# Dice_Simulator.net
KiCad netlist of a schematic drawn in EAGLE
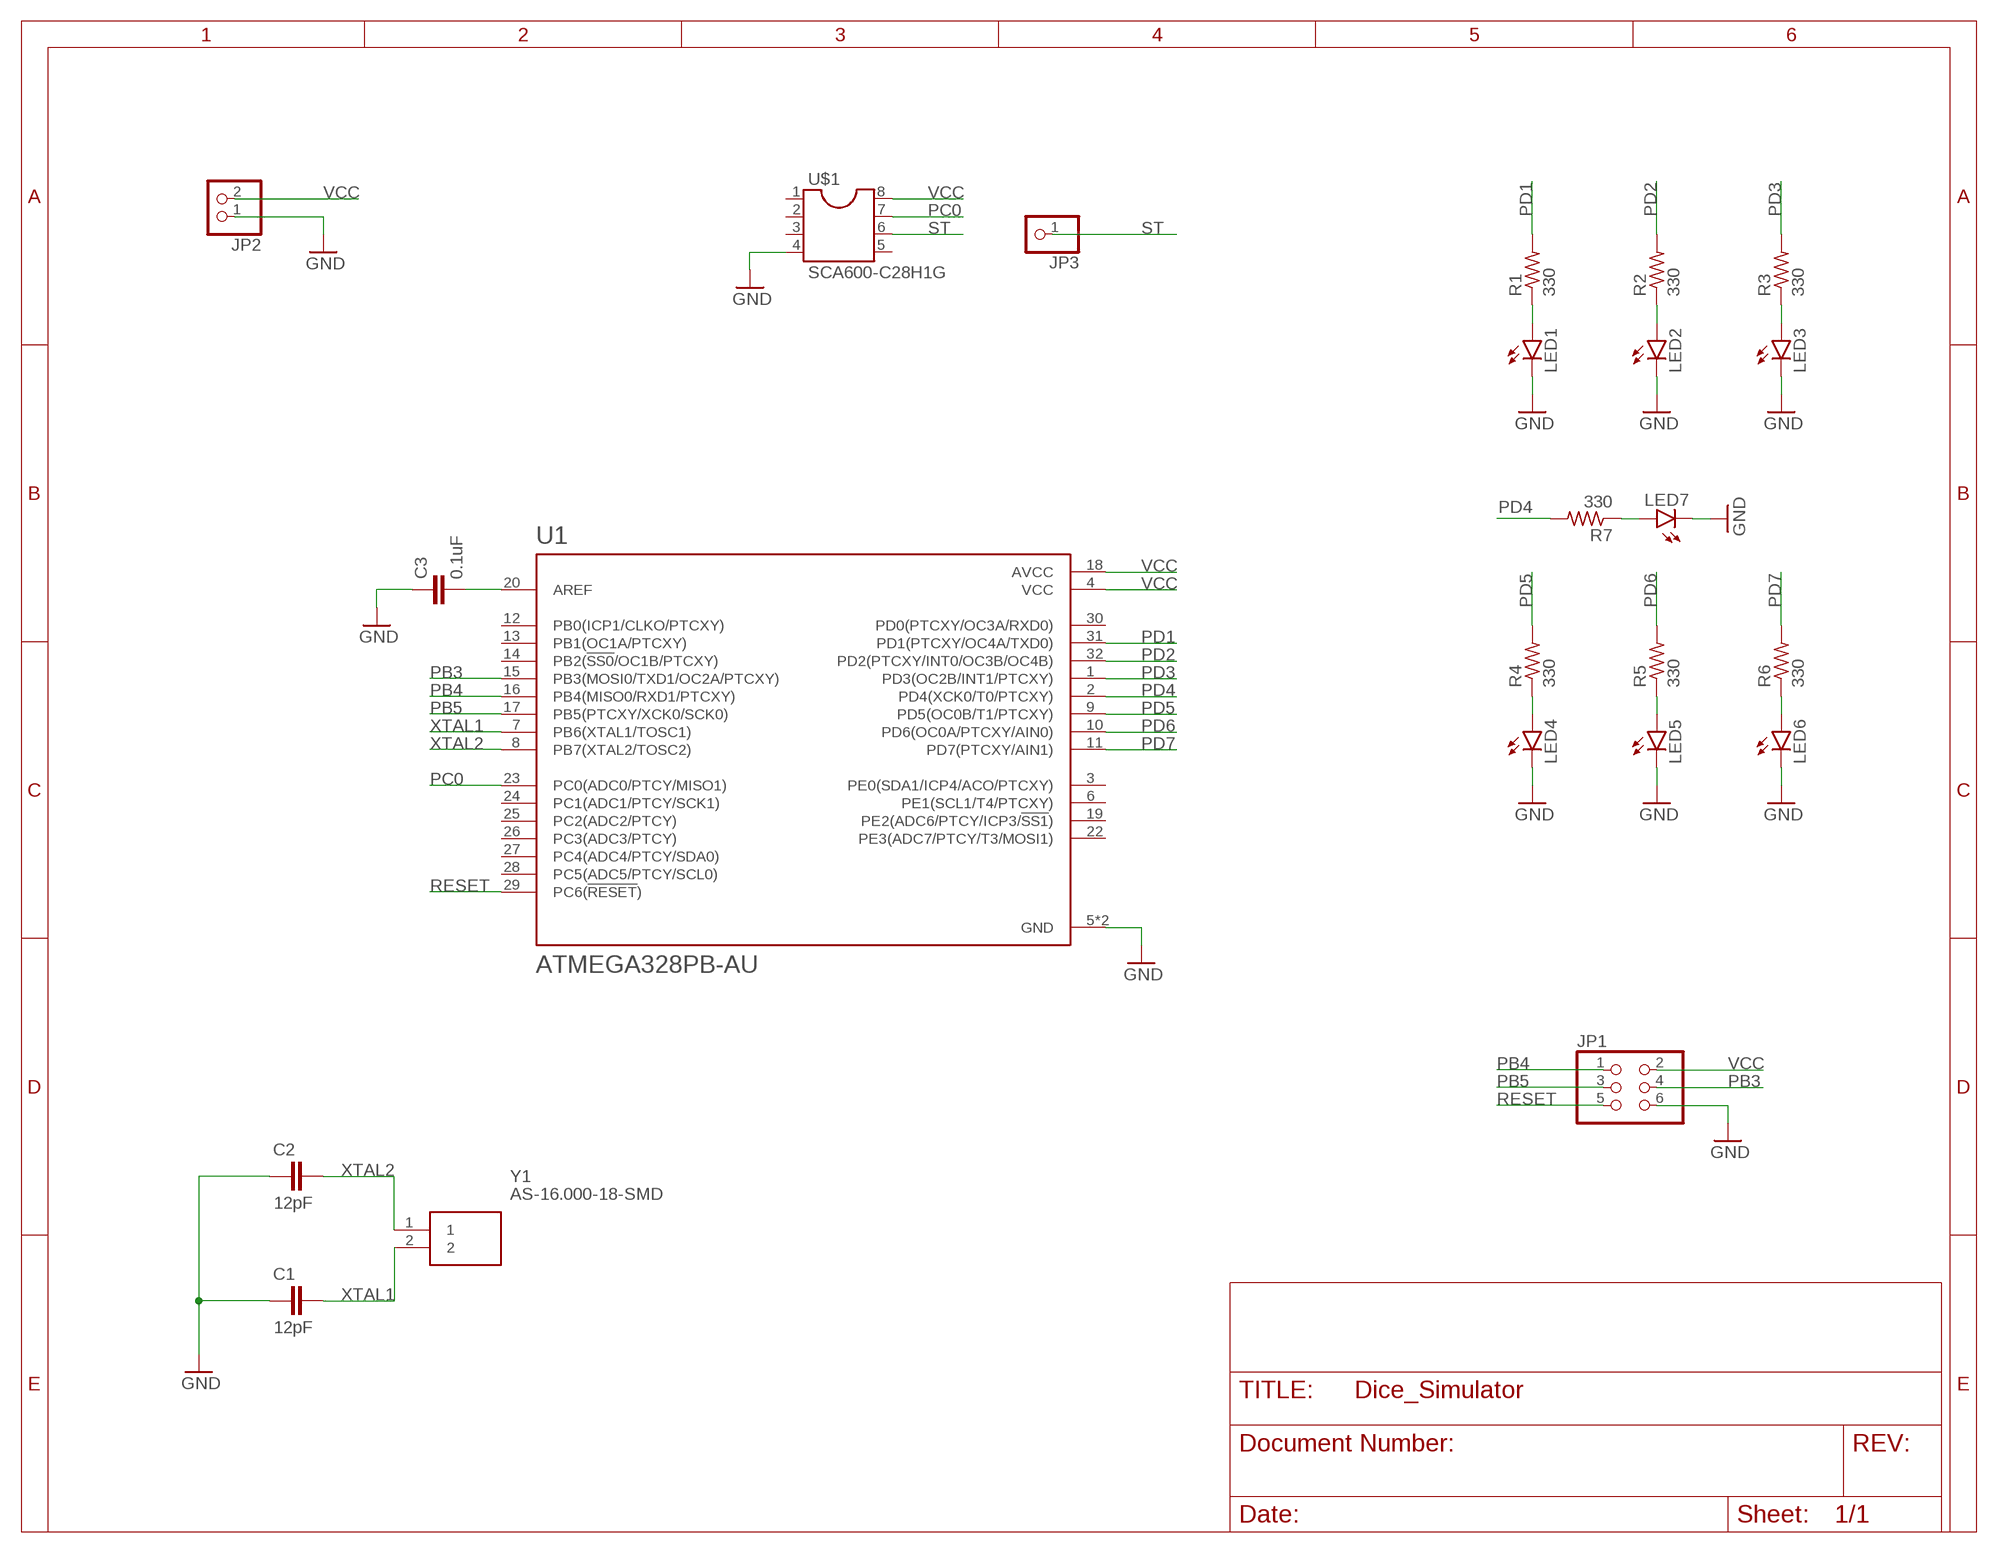
[diagram p0: schematic, sheet 1]

(export (version "E")
  (design (tool "Eeschema 10.0.6"))
  (components
    (comp (ref "C1")
      (value "12pF")
      (footprint "eagle-import:C0805")
      (libsource (lib "eagle-import") (part "C-EUC0805"))
    )
    (comp (ref "C2")
      (value "12pF")
      (footprint "eagle-import:C0805")
      (libsource (lib "eagle-import") (part "C-EUC0805"))
    )
    (comp (ref "C3")
      (value "0.1uF")
      (footprint "eagle-import:C0805")
      (libsource (lib "eagle-import") (part "C-EUC0805"))
    )
    (comp (ref "JP1")
      (value "PINHD-2X3")
      (footprint "eagle-import:2X03")
      (libsource (lib "eagle-import") (part "PINHD-2X3"))
    )
    (comp (ref "JP2")
      (value "PINHD-1X2")
      (footprint "eagle-import:1X02")
      (libsource (lib "eagle-import") (part "PINHD-1X2"))
    )
    (comp (ref "JP3")
      (value "PINHD-1X1")
      (footprint "eagle-import:1X01")
      (libsource (lib "eagle-import") (part "PINHD-1X1"))
    )
    (comp (ref "LED1")
      (value "LEDCHIPLED_0805")
      (footprint "eagle-import:CHIPLED_0805")
      (libsource (lib "eagle-import") (part "LEDCHIPLED_0805"))
    )
    (comp (ref "LED2")
      (value "LEDCHIPLED_0805")
      (footprint "eagle-import:CHIPLED_0805")
      (libsource (lib "eagle-import") (part "LEDCHIPLED_0805"))
    )
    (comp (ref "LED3")
      (value "LEDCHIPLED_0805")
      (footprint "eagle-import:CHIPLED_0805")
      (libsource (lib "eagle-import") (part "LEDCHIPLED_0805"))
    )
    (comp (ref "LED4")
      (value "LEDCHIPLED_0805")
      (footprint "eagle-import:CHIPLED_0805")
      (libsource (lib "eagle-import") (part "LEDCHIPLED_0805"))
    )
    (comp (ref "LED5")
      (value "LEDCHIPLED_0805")
      (footprint "eagle-import:CHIPLED_0805")
      (libsource (lib "eagle-import") (part "LEDCHIPLED_0805"))
    )
    (comp (ref "LED6")
      (value "LEDCHIPLED_0805")
      (footprint "eagle-import:CHIPLED_0805")
      (libsource (lib "eagle-import") (part "LEDCHIPLED_0805"))
    )
    (comp (ref "LED7")
      (value "LEDCHIPLED_0805")
      (footprint "eagle-import:CHIPLED_0805")
      (libsource (lib "eagle-import") (part "LEDCHIPLED_0805"))
    )
    (comp (ref "R1")
      (value "330")
      (footprint "eagle-import:M0805")
      (libsource (lib "eagle-import") (part "R-US_M0805"))
    )
    (comp (ref "R2")
      (value "330")
      (footprint "eagle-import:M0805")
      (libsource (lib "eagle-import") (part "R-US_M0805"))
    )
    (comp (ref "R3")
      (value "330")
      (footprint "eagle-import:M0805")
      (libsource (lib "eagle-import") (part "R-US_M0805"))
    )
    (comp (ref "R4")
      (value "330")
      (footprint "eagle-import:M0805")
      (libsource (lib "eagle-import") (part "R-US_M0805"))
    )
    (comp (ref "R5")
      (value "330")
      (footprint "eagle-import:M0805")
      (libsource (lib "eagle-import") (part "R-US_M0805"))
    )
    (comp (ref "R6")
      (value "330")
      (footprint "eagle-import:M0805")
      (libsource (lib "eagle-import") (part "R-US_M0805"))
    )
    (comp (ref "R7")
      (value "330")
      (footprint "eagle-import:M0805")
      (libsource (lib "eagle-import") (part "R-US_M0805"))
    )
    (comp (ref "U$1")
      (value "SCA600-C28H1G")
      (footprint "eagle-import:SCA600-C28H1G")
      (libsource (lib "eagle-import") (part "SCA600-C28H1G"))
    )
    (comp (ref "U1")
      (value "ATMEGA328PB-AU")
      (footprint "eagle-import:QFP80P900X900X120-32N")
      (fields (field (name "MF") "Microchip Technology / Atmel"))
      (libsource (lib "eagle-import") (part "ATMEGA328PB-AU"))
    )
    (comp (ref "Y1")
      (value "AS-16.000-18-SMD")
      (footprint "eagle-import:HC-49")
      (fields (field (name "RS_PART_NUMBER") "7037129P"))
      (libsource (lib "eagle-import") (part "AS-16.000-18-SMD"))
    )
  )
  (nets
    (net (code "1") (name "/PB3") (class "Default")
      (node (ref "JP1") (pin "4") (pinfunction "4_4") (pintype "passive"))
      (node (ref "U1") (pin "15") (pinfunction "PB3(MOSI0/TXD1/OC2A/PTCXY)_15") (pintype "bidirectional"))
    )
    (net (code "2") (name "/PB4") (class "Default")
      (node (ref "JP1") (pin "1") (pinfunction "1_1") (pintype "passive"))
      (node (ref "U1") (pin "16") (pinfunction "PB4(MISO0/RXD1/PTCXY)_16") (pintype "bidirectional"))
    )
    (net (code "3") (name "/PB5") (class "Default")
      (node (ref "JP1") (pin "3") (pinfunction "3_3") (pintype "passive"))
      (node (ref "U1") (pin "17") (pinfunction "PB5(PTCXY/XCK0/SCK0)_17") (pintype "bidirectional"))
    )
    (net (code "4") (name "/PC0") (class "Default")
      (node (ref "U$1") (pin "7") (pinfunction "7_7") (pintype "passive"))
      (node (ref "U1") (pin "23") (pinfunction "PC0(ADC0/PTCY/MISO1)_23") (pintype "bidirectional"))
    )
    (net (code "5") (name "/PD1") (class "Default")
      (node (ref "R1") (pin "2") (pinfunction "2_2") (pintype "passive"))
      (node (ref "U1") (pin "31") (pinfunction "PD1(PTCXY/OC4A/TXD0)_31") (pintype "bidirectional"))
    )
    (net (code "6") (name "/PD2") (class "Default")
      (node (ref "R2") (pin "2") (pinfunction "2_2") (pintype "passive"))
      (node (ref "U1") (pin "32") (pinfunction "PD2(PTCXY/INT0/OC3B/OC4B)_32") (pintype "bidirectional"))
    )
    (net (code "7") (name "/PD3") (class "Default")
      (node (ref "R3") (pin "2") (pinfunction "2_2") (pintype "passive"))
      (node (ref "U1") (pin "1") (pinfunction "PD3(OC2B/INT1/PTCXY)_1") (pintype "bidirectional"))
    )
    (net (code "8") (name "/PD4") (class "Default")
      (node (ref "R7") (pin "2") (pinfunction "2_2") (pintype "passive"))
      (node (ref "U1") (pin "2") (pinfunction "PD4(XCK0/T0/PTCXY)_2") (pintype "bidirectional"))
    )
    (net (code "9") (name "/PD5") (class "Default")
      (node (ref "R4") (pin "2") (pinfunction "2_2") (pintype "passive"))
      (node (ref "U1") (pin "9") (pinfunction "PD5(OC0B/T1/PTCXY)_9") (pintype "bidirectional"))
    )
    (net (code "10") (name "/PD6") (class "Default")
      (node (ref "R5") (pin "2") (pinfunction "2_2") (pintype "passive"))
      (node (ref "U1") (pin "10") (pinfunction "PD6(OC0A/PTCXY/AIN0)_10") (pintype "bidirectional"))
    )
    (net (code "11") (name "/PD7") (class "Default")
      (node (ref "R6") (pin "2") (pinfunction "2_2") (pintype "passive"))
      (node (ref "U1") (pin "11") (pinfunction "PD7(PTCXY/AIN1)_11") (pintype "bidirectional"))
    )
    (net (code "12") (name "/RESET") (class "Default")
      (node (ref "JP1") (pin "5") (pinfunction "5_5") (pintype "passive"))
      (node (ref "U1") (pin "29") (pinfunction "PC6(~{RESET})_29") (pintype "bidirectional"))
    )
    (net (code "13") (name "/ST") (class "Default")
      (node (ref "JP3") (pin "1") (pinfunction "1_1") (pintype "passive"))
      (node (ref "U$1") (pin "6") (pinfunction "6_6") (pintype "passive"))
    )
    (net (code "14") (name "/VCC") (class "Default")
      (node (ref "JP1") (pin "2") (pinfunction "2_2") (pintype "passive"))
      (node (ref "JP2") (pin "2") (pinfunction "2_2") (pintype "passive"))
      (node (ref "U$1") (pin "8") (pinfunction "8_8") (pintype "passive"))
      (node (ref "U1") (pin "18") (pinfunction "AVCC_18") (pintype "power_in"))
      (node (ref "U1") (pin "4") (pinfunction "VCC_4") (pintype "power_in"))
    )
    (net (code "15") (name "/XTAL1") (class "Default")
      (node (ref "C1") (pin "2") (pinfunction "2_2") (pintype "passive"))
      (node (ref "U1") (pin "7") (pinfunction "PB6(XTAL1/TOSC1)_7") (pintype "bidirectional"))
      (node (ref "Y1") (pin "2") (pinfunction "2_2") (pintype "bidirectional"))
    )
    (net (code "16") (name "/XTAL2") (class "Default")
      (node (ref "C2") (pin "2") (pinfunction "2_2") (pintype "passive"))
      (node (ref "U1") (pin "8") (pinfunction "PB7(XTAL2/TOSC2)_8") (pintype "bidirectional"))
      (node (ref "Y1") (pin "1") (pinfunction "1_1") (pintype "bidirectional"))
    )
    (net (code "17") (name "GND") (class "Default")
      (node (ref "C1") (pin "1") (pinfunction "1_1") (pintype "passive"))
      (node (ref "C2") (pin "1") (pinfunction "1_1") (pintype "passive"))
      (node (ref "C3") (pin "1") (pinfunction "1_1") (pintype "passive"))
      (node (ref "JP1") (pin "6") (pinfunction "6_6") (pintype "passive"))
      (node (ref "JP2") (pin "1") (pinfunction "1_1") (pintype "passive"))
      (node (ref "LED1") (pin "C") (pinfunction "C_C") (pintype "passive"))
      (node (ref "LED2") (pin "C") (pinfunction "C_C") (pintype "passive"))
      (node (ref "LED3") (pin "C") (pinfunction "C_C") (pintype "passive"))
      (node (ref "LED4") (pin "C") (pinfunction "C_C") (pintype "passive"))
      (node (ref "LED5") (pin "C") (pinfunction "C_C") (pintype "passive"))
      (node (ref "LED6") (pin "C") (pinfunction "C_C") (pintype "passive"))
      (node (ref "LED7") (pin "C") (pinfunction "C_C") (pintype "passive"))
      (node (ref "U$1") (pin "4") (pinfunction "4_4") (pintype "passive"))
      (node (ref "U1") (pin "21") (pinfunction "GND_21") (pintype "power_in"))
      (node (ref "U1") (pin "5") (pinfunction "GND_5") (pintype "power_in"))
    )
    (net (code "18") (name "Net-(LED1-PadA)") (class "Default")
      (node (ref "LED1") (pin "A") (pinfunction "A_A") (pintype "passive"))
      (node (ref "R1") (pin "1") (pinfunction "1_1") (pintype "passive"))
    )
    (net (code "19") (name "Net-(LED2-PadA)") (class "Default")
      (node (ref "LED2") (pin "A") (pinfunction "A_A") (pintype "passive"))
      (node (ref "R2") (pin "1") (pinfunction "1_1") (pintype "passive"))
    )
    (net (code "20") (name "Net-(LED3-PadA)") (class "Default")
      (node (ref "LED3") (pin "A") (pinfunction "A_A") (pintype "passive"))
      (node (ref "R3") (pin "1") (pinfunction "1_1") (pintype "passive"))
    )
    (net (code "21") (name "Net-(LED4-PadA)") (class "Default")
      (node (ref "LED4") (pin "A") (pinfunction "A_A") (pintype "passive"))
      (node (ref "R4") (pin "1") (pinfunction "1_1") (pintype "passive"))
    )
    (net (code "22") (name "Net-(LED5-PadA)") (class "Default")
      (node (ref "LED5") (pin "A") (pinfunction "A_A") (pintype "passive"))
      (node (ref "R5") (pin "1") (pinfunction "1_1") (pintype "passive"))
    )
    (net (code "23") (name "Net-(LED6-PadA)") (class "Default")
      (node (ref "LED6") (pin "A") (pinfunction "A_A") (pintype "passive"))
      (node (ref "R6") (pin "1") (pinfunction "1_1") (pintype "passive"))
    )
    (net (code "24") (name "Net-(LED7-PadA)") (class "Default")
      (node (ref "LED7") (pin "A") (pinfunction "A_A") (pintype "passive"))
      (node (ref "R7") (pin "1") (pinfunction "1_1") (pintype "passive"))
    )
    (net (code "25") (name "Net-(U1-AREF)") (class "Default")
      (node (ref "C3") (pin "2") (pinfunction "2_2") (pintype "passive"))
      (node (ref "U1") (pin "20") (pinfunction "AREF_20") (pintype "input"))
    )
    (net (code "26") (name "unconnected-(U$1-Pad1)") (class "Default")
      (node (ref "U$1") (pin "1") (pinfunction "1_1") (pintype "passive"))
    )
    (net (code "27") (name "unconnected-(U$1-Pad2)") (class "Default")
      (node (ref "U$1") (pin "2") (pinfunction "2_2") (pintype "passive"))
    )
    (net (code "28") (name "unconnected-(U$1-Pad3)") (class "Default")
      (node (ref "U$1") (pin "3") (pinfunction "3_3") (pintype "passive"))
    )
    (net (code "29") (name "unconnected-(U$1-Pad5)") (class "Default")
      (node (ref "U$1") (pin "5") (pinfunction "5_5") (pintype "passive"))
    )
    (net (code "30") (name "unconnected-(U1-PB0(ICP1{slash}CLKO{slash}PTCXY)-Pad12)") (class "Default")
      (node (ref "U1") (pin "12") (pinfunction "PB0(ICP1/CLKO/PTCXY)_12") (pintype "bidirectional"))
    )
    (net (code "31") (name "unconnected-(U1-PB1(OC1A{slash}PTCXY)-Pad13)") (class "Default")
      (node (ref "U1") (pin "13") (pinfunction "PB1(OC1A/PTCXY)_13") (pintype "bidirectional"))
    )
    (net (code "32") (name "unconnected-(U1-PB2(~{SS0}{slash}OC1B{slash}PTCXY)-Pad14)") (class "Default")
      (node (ref "U1") (pin "14") (pinfunction "PB2(~{SS0}/OC1B/PTCXY)_14") (pintype "bidirectional"))
    )
    (net (code "33") (name "unconnected-(U1-PC1(ADC1{slash}PTCY{slash}SCK1)-Pad24)") (class "Default")
      (node (ref "U1") (pin "24") (pinfunction "PC1(ADC1/PTCY/SCK1)_24") (pintype "bidirectional"))
    )
    (net (code "34") (name "unconnected-(U1-PC2(ADC2{slash}PTCY)-Pad25)") (class "Default")
      (node (ref "U1") (pin "25") (pinfunction "PC2(ADC2/PTCY)_25") (pintype "bidirectional"))
    )
    (net (code "35") (name "unconnected-(U1-PC3(ADC3{slash}PTCY)-Pad26)") (class "Default")
      (node (ref "U1") (pin "26") (pinfunction "PC3(ADC3/PTCY)_26") (pintype "bidirectional"))
    )
    (net (code "36") (name "unconnected-(U1-PC4(ADC4{slash}PTCY{slash}SDA0)-Pad27)") (class "Default")
      (node (ref "U1") (pin "27") (pinfunction "PC4(ADC4/PTCY/SDA0)_27") (pintype "bidirectional"))
    )
    (net (code "37") (name "unconnected-(U1-PC5(ADC5{slash}PTCY{slash}SCL0)-Pad28)") (class "Default")
      (node (ref "U1") (pin "28") (pinfunction "PC5(ADC5/PTCY/SCL0)_28") (pintype "bidirectional"))
    )
    (net (code "38") (name "unconnected-(U1-PD0(PTCXY{slash}OC3A{slash}RXD0)-Pad30)") (class "Default")
      (node (ref "U1") (pin "30") (pinfunction "PD0(PTCXY/OC3A/RXD0)_30") (pintype "bidirectional"))
    )
    (net (code "39") (name "unconnected-(U1-PE0(SDA1{slash}ICP4{slash}ACO{slash}PTCXY)-Pad3)") (class "Default")
      (node (ref "U1") (pin "3") (pinfunction "PE0(SDA1/ICP4/ACO/PTCXY)_3") (pintype "bidirectional"))
    )
    (net (code "40") (name "unconnected-(U1-PE1(SCL1{slash}T4{slash}PTCXY)-Pad6)") (class "Default")
      (node (ref "U1") (pin "6") (pinfunction "PE1(SCL1/T4/PTCXY)_6") (pintype "bidirectional"))
    )
    (net (code "41") (name "unconnected-(U1-PE2(ADC6{slash}PTCY{slash}ICP3{slash}~{SS1})-Pad19)") (class "Default")
      (node (ref "U1") (pin "19") (pinfunction "PE2(ADC6/PTCY/ICP3/~{SS1})_19") (pintype "bidirectional"))
    )
    (net (code "42") (name "unconnected-(U1-PE3(ADC7{slash}PTCY{slash}T3{slash}MOSI1)-Pad22)") (class "Default")
      (node (ref "U1") (pin "22") (pinfunction "PE3(ADC7/PTCY/T3/MOSI1)_22") (pintype "bidirectional"))
    )
  )
)
